# APA106_uno_shield.net
KiCad netlist of a schematic drawn in EAGLE
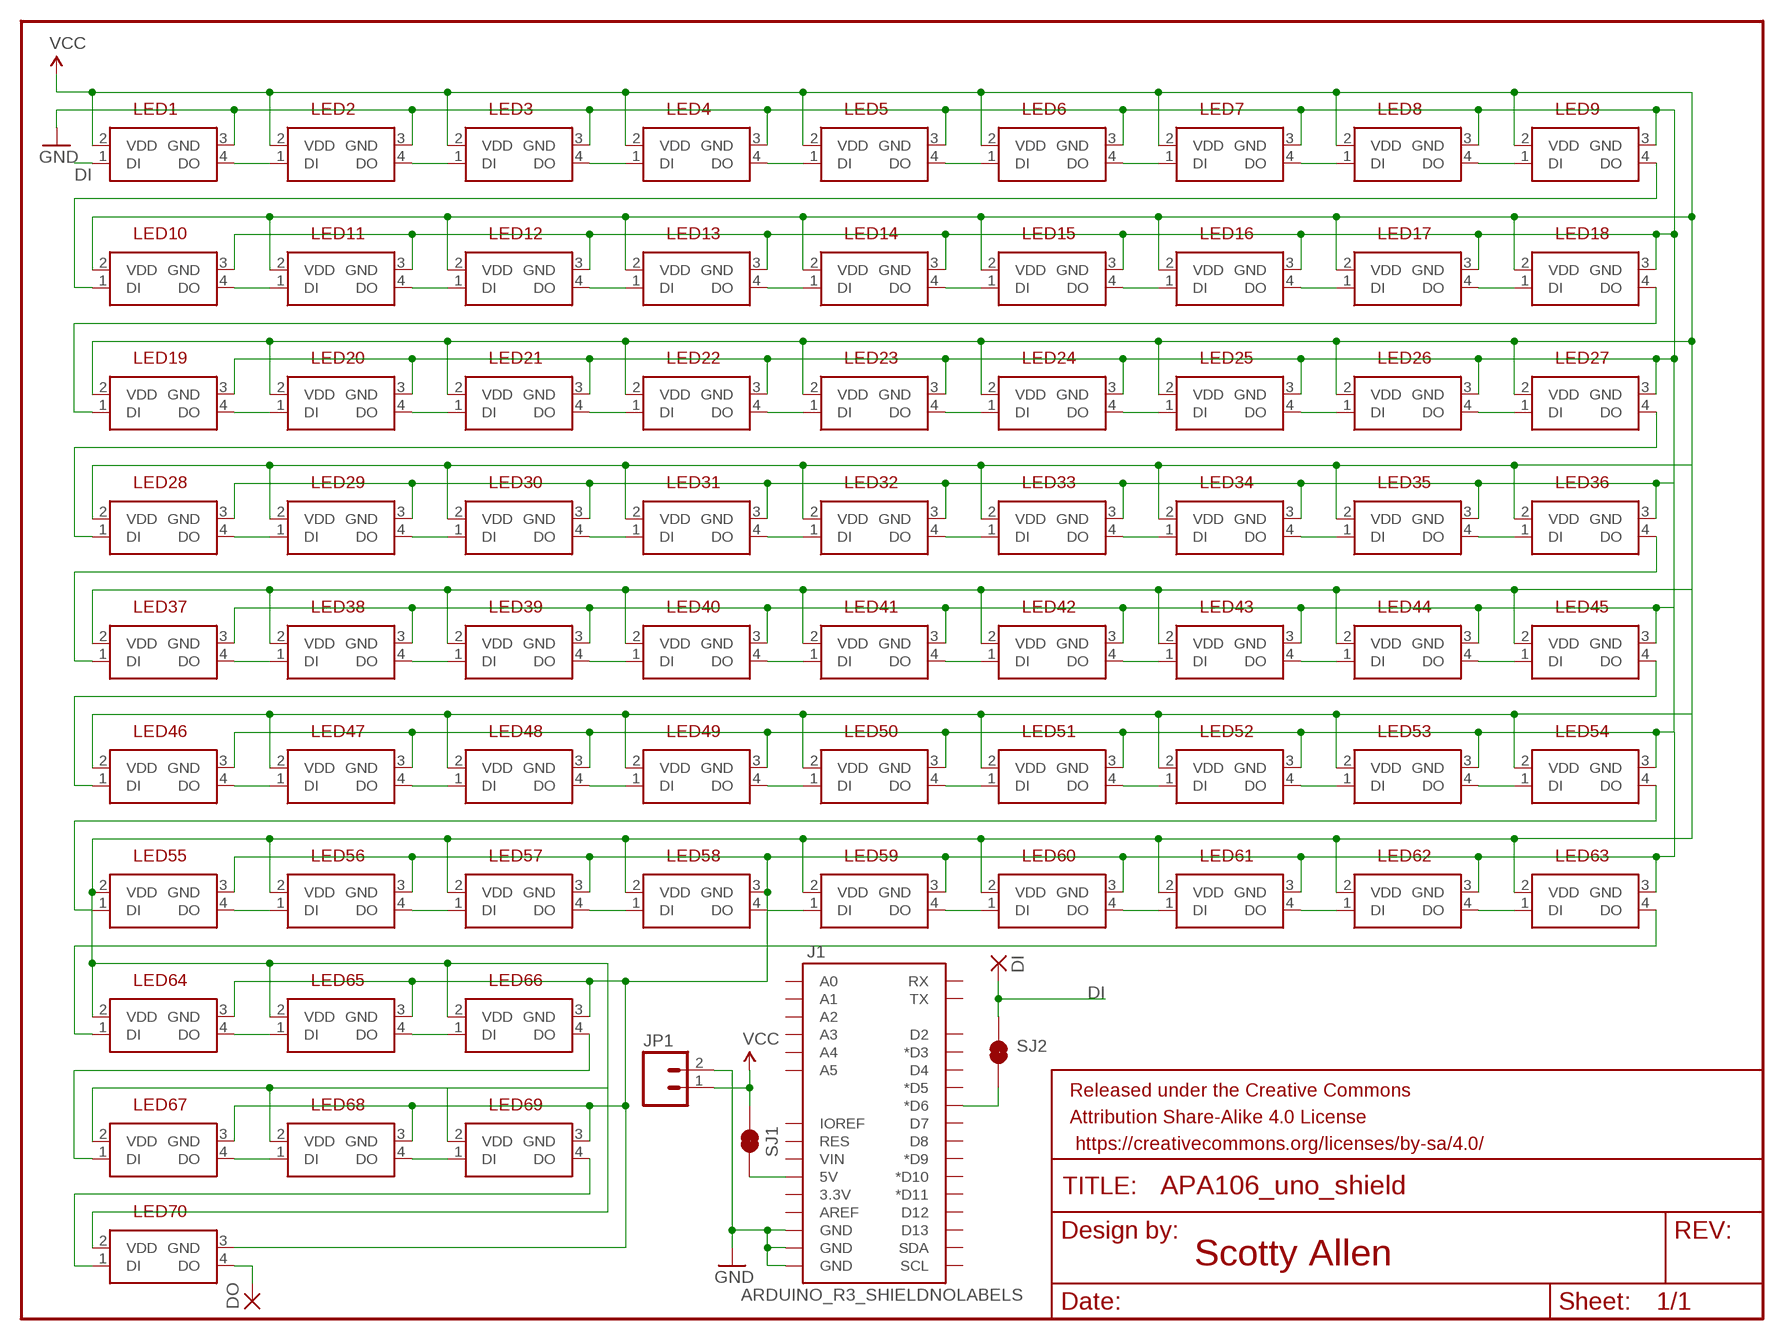
[diagram p0: schematic, sheet 1]

(export (version "E")
  (design (tool "Eeschema 10.0.6"))
  (components
    (comp (ref "DI")
      (value "1,6/0,9")
      (footprint "eagle-import:1,6_0,9")
      (libsource (lib "eagle-import") (part "1,6/0,9"))
    )
    (comp (ref "DO")
      (value "1,6/0,9")
      (footprint "eagle-import:1,6_0,9")
      (libsource (lib "eagle-import") (part "1,6/0,9"))
    )
    (comp (ref "FRAME1")
      (value "FRAME-LETTER")
      (footprint "eagle-import:CREATIVE_COMMONS")
      (libsource (lib "eagle-import") (part "FRAME-LETTER"))
    )
    (comp (ref "J1")
      (value "ARDUINO_R3_SHIELDNOLABELS")
      (footprint "eagle-import:UNO_R3_SHIELD_NOLABELS")
      (libsource (lib "eagle-import") (part "ARDUINO_R3_SHIELDNOLABELS"))
    )
    (comp (ref "JP1")
      (value "M02PTH")
      (footprint "eagle-import:1X02")
      (libsource (lib "eagle-import") (part "M02PTH"))
    )
    (comp (ref "LED1")
      (value "LED-APA106HOLE-OFFSET-SPREAD")
      (footprint "eagle-import:LED-5MM-4PIN-HOLE-OFFSET-SPREAD")
      (libsource (lib "eagle-import") (part "LED-APA106HOLE-OFFSET-SPREAD"))
    )
    (comp (ref "LED2")
      (value "LED-APA106HOLE-OFFSET-SPREAD")
      (footprint "eagle-import:LED-5MM-4PIN-HOLE-OFFSET-SPREAD")
      (libsource (lib "eagle-import") (part "LED-APA106HOLE-OFFSET-SPREAD"))
    )
    (comp (ref "LED3")
      (value "LED-APA106HOLE-OFFSET-SPREAD")
      (footprint "eagle-import:LED-5MM-4PIN-HOLE-OFFSET-SPREAD")
      (libsource (lib "eagle-import") (part "LED-APA106HOLE-OFFSET-SPREAD"))
    )
    (comp (ref "LED4")
      (value "LED-APA106HOLE-OFFSET-SPREAD")
      (footprint "eagle-import:LED-5MM-4PIN-HOLE-OFFSET-SPREAD")
      (libsource (lib "eagle-import") (part "LED-APA106HOLE-OFFSET-SPREAD"))
    )
    (comp (ref "LED5")
      (value "LED-APA106HOLE-OFFSET-SPREAD")
      (footprint "eagle-import:LED-5MM-4PIN-HOLE-OFFSET-SPREAD")
      (libsource (lib "eagle-import") (part "LED-APA106HOLE-OFFSET-SPREAD"))
    )
    (comp (ref "LED6")
      (value "LED-APA106HOLE-OFFSET-SPREAD")
      (footprint "eagle-import:LED-5MM-4PIN-HOLE-OFFSET-SPREAD")
      (libsource (lib "eagle-import") (part "LED-APA106HOLE-OFFSET-SPREAD"))
    )
    (comp (ref "LED7")
      (value "LED-APA106HOLE-OFFSET-SPREAD")
      (footprint "eagle-import:LED-5MM-4PIN-HOLE-OFFSET-SPREAD")
      (libsource (lib "eagle-import") (part "LED-APA106HOLE-OFFSET-SPREAD"))
    )
    (comp (ref "LED8")
      (value "LED-APA106HOLE-OFFSET-SPREAD")
      (footprint "eagle-import:LED-5MM-4PIN-HOLE-OFFSET-SPREAD")
      (libsource (lib "eagle-import") (part "LED-APA106HOLE-OFFSET-SPREAD"))
    )
    (comp (ref "LED9")
      (value "LED-APA106HOLE-OFFSET-SPREAD")
      (footprint "eagle-import:LED-5MM-4PIN-HOLE-OFFSET-SPREAD")
      (libsource (lib "eagle-import") (part "LED-APA106HOLE-OFFSET-SPREAD"))
    )
    (comp (ref "LED10")
      (value "LED-APA106HOLE-OFFSET-SPREAD")
      (footprint "eagle-import:LED-5MM-4PIN-HOLE-OFFSET-SPREAD")
      (libsource (lib "eagle-import") (part "LED-APA106HOLE-OFFSET-SPREAD"))
    )
    (comp (ref "LED11")
      (value "LED-APA106HOLE-OFFSET-SPREAD")
      (footprint "eagle-import:LED-5MM-4PIN-HOLE-OFFSET-SPREAD")
      (libsource (lib "eagle-import") (part "LED-APA106HOLE-OFFSET-SPREAD"))
    )
    (comp (ref "LED12")
      (value "LED-APA106HOLE-OFFSET-SPREAD")
      (footprint "eagle-import:LED-5MM-4PIN-HOLE-OFFSET-SPREAD")
      (libsource (lib "eagle-import") (part "LED-APA106HOLE-OFFSET-SPREAD"))
    )
    (comp (ref "LED13")
      (value "LED-APA106HOLE-OFFSET-SPREAD")
      (footprint "eagle-import:LED-5MM-4PIN-HOLE-OFFSET-SPREAD")
      (libsource (lib "eagle-import") (part "LED-APA106HOLE-OFFSET-SPREAD"))
    )
    (comp (ref "LED14")
      (value "LED-APA106HOLE-OFFSET-SPREAD")
      (footprint "eagle-import:LED-5MM-4PIN-HOLE-OFFSET-SPREAD")
      (libsource (lib "eagle-import") (part "LED-APA106HOLE-OFFSET-SPREAD"))
    )
    (comp (ref "LED15")
      (value "LED-APA106HOLE-OFFSET-SPREAD")
      (footprint "eagle-import:LED-5MM-4PIN-HOLE-OFFSET-SPREAD")
      (libsource (lib "eagle-import") (part "LED-APA106HOLE-OFFSET-SPREAD"))
    )
    (comp (ref "LED16")
      (value "LED-APA106HOLE-OFFSET-SPREAD")
      (footprint "eagle-import:LED-5MM-4PIN-HOLE-OFFSET-SPREAD")
      (libsource (lib "eagle-import") (part "LED-APA106HOLE-OFFSET-SPREAD"))
    )
    (comp (ref "LED17")
      (value "LED-APA106HOLE-OFFSET-SPREAD")
      (footprint "eagle-import:LED-5MM-4PIN-HOLE-OFFSET-SPREAD")
      (libsource (lib "eagle-import") (part "LED-APA106HOLE-OFFSET-SPREAD"))
    )
    (comp (ref "LED18")
      (value "LED-APA106HOLE-OFFSET-SPREAD")
      (footprint "eagle-import:LED-5MM-4PIN-HOLE-OFFSET-SPREAD")
      (libsource (lib "eagle-import") (part "LED-APA106HOLE-OFFSET-SPREAD"))
    )
    (comp (ref "LED19")
      (value "LED-APA106HOLE-OFFSET-SPREAD")
      (footprint "eagle-import:LED-5MM-4PIN-HOLE-OFFSET-SPREAD")
      (libsource (lib "eagle-import") (part "LED-APA106HOLE-OFFSET-SPREAD"))
    )
    (comp (ref "LED20")
      (value "LED-APA106HOLE-OFFSET-SPREAD")
      (footprint "eagle-import:LED-5MM-4PIN-HOLE-OFFSET-SPREAD")
      (libsource (lib "eagle-import") (part "LED-APA106HOLE-OFFSET-SPREAD"))
    )
    (comp (ref "LED21")
      (value "LED-APA106HOLE-OFFSET-SPREAD")
      (footprint "eagle-import:LED-5MM-4PIN-HOLE-OFFSET-SPREAD")
      (libsource (lib "eagle-import") (part "LED-APA106HOLE-OFFSET-SPREAD"))
    )
    (comp (ref "LED22")
      (value "LED-APA106HOLE-OFFSET-SPREAD")
      (footprint "eagle-import:LED-5MM-4PIN-HOLE-OFFSET-SPREAD")
      (libsource (lib "eagle-import") (part "LED-APA106HOLE-OFFSET-SPREAD"))
    )
    (comp (ref "LED23")
      (value "LED-APA106HOLE-OFFSET-SPREAD")
      (footprint "eagle-import:LED-5MM-4PIN-HOLE-OFFSET-SPREAD")
      (libsource (lib "eagle-import") (part "LED-APA106HOLE-OFFSET-SPREAD"))
    )
    (comp (ref "LED24")
      (value "LED-APA106HOLE-OFFSET-SPREAD")
      (footprint "eagle-import:LED-5MM-4PIN-HOLE-OFFSET-SPREAD")
      (libsource (lib "eagle-import") (part "LED-APA106HOLE-OFFSET-SPREAD"))
    )
    (comp (ref "LED25")
      (value "LED-APA106HOLE-OFFSET-SPREAD")
      (footprint "eagle-import:LED-5MM-4PIN-HOLE-OFFSET-SPREAD")
      (libsource (lib "eagle-import") (part "LED-APA106HOLE-OFFSET-SPREAD"))
    )
    (comp (ref "LED26")
      (value "LED-APA106HOLE-OFFSET-SPREAD")
      (footprint "eagle-import:LED-5MM-4PIN-HOLE-OFFSET-SPREAD")
      (libsource (lib "eagle-import") (part "LED-APA106HOLE-OFFSET-SPREAD"))
    )
    (comp (ref "LED27")
      (value "LED-APA106HOLE-OFFSET-SPREAD")
      (footprint "eagle-import:LED-5MM-4PIN-HOLE-OFFSET-SPREAD")
      (libsource (lib "eagle-import") (part "LED-APA106HOLE-OFFSET-SPREAD"))
    )
    (comp (ref "LED28")
      (value "LED-APA106HOLE-OFFSET-SPREAD")
      (footprint "eagle-import:LED-5MM-4PIN-HOLE-OFFSET-SPREAD")
      (libsource (lib "eagle-import") (part "LED-APA106HOLE-OFFSET-SPREAD"))
    )
    (comp (ref "LED29")
      (value "LED-APA106HOLE-OFFSET-SPREAD")
      (footprint "eagle-import:LED-5MM-4PIN-HOLE-OFFSET-SPREAD")
      (libsource (lib "eagle-import") (part "LED-APA106HOLE-OFFSET-SPREAD"))
    )
    (comp (ref "LED30")
      (value "LED-APA106HOLE-OFFSET-SPREAD")
      (footprint "eagle-import:LED-5MM-4PIN-HOLE-OFFSET-SPREAD")
      (libsource (lib "eagle-import") (part "LED-APA106HOLE-OFFSET-SPREAD"))
    )
    (comp (ref "LED31")
      (value "LED-APA106HOLE-OFFSET-SPREAD")
      (footprint "eagle-import:LED-5MM-4PIN-HOLE-OFFSET-SPREAD")
      (libsource (lib "eagle-import") (part "LED-APA106HOLE-OFFSET-SPREAD"))
    )
    (comp (ref "LED32")
      (value "LED-APA106HOLE-OFFSET-SPREAD")
      (footprint "eagle-import:LED-5MM-4PIN-HOLE-OFFSET-SPREAD")
      (libsource (lib "eagle-import") (part "LED-APA106HOLE-OFFSET-SPREAD"))
    )
    (comp (ref "LED33")
      (value "LED-APA106HOLE-OFFSET-SPREAD")
      (footprint "eagle-import:LED-5MM-4PIN-HOLE-OFFSET-SPREAD")
      (libsource (lib "eagle-import") (part "LED-APA106HOLE-OFFSET-SPREAD"))
    )
    (comp (ref "LED34")
      (value "LED-APA106HOLE-OFFSET-SPREAD")
      (footprint "eagle-import:LED-5MM-4PIN-HOLE-OFFSET-SPREAD")
      (libsource (lib "eagle-import") (part "LED-APA106HOLE-OFFSET-SPREAD"))
    )
    (comp (ref "LED35")
      (value "LED-APA106HOLE-OFFSET-SPREAD")
      (footprint "eagle-import:LED-5MM-4PIN-HOLE-OFFSET-SPREAD")
      (libsource (lib "eagle-import") (part "LED-APA106HOLE-OFFSET-SPREAD"))
    )
    (comp (ref "LED36")
      (value "LED-APA106HOLE-OFFSET-SPREAD")
      (footprint "eagle-import:LED-5MM-4PIN-HOLE-OFFSET-SPREAD")
      (libsource (lib "eagle-import") (part "LED-APA106HOLE-OFFSET-SPREAD"))
    )
    (comp (ref "LED37")
      (value "LED-APA106HOLE-OFFSET-SPREAD")
      (footprint "eagle-import:LED-5MM-4PIN-HOLE-OFFSET-SPREAD")
      (libsource (lib "eagle-import") (part "LED-APA106HOLE-OFFSET-SPREAD"))
    )
    (comp (ref "LED38")
      (value "LED-APA106HOLE-OFFSET-SPREAD")
      (footprint "eagle-import:LED-5MM-4PIN-HOLE-OFFSET-SPREAD")
      (libsource (lib "eagle-import") (part "LED-APA106HOLE-OFFSET-SPREAD"))
    )
    (comp (ref "LED39")
      (value "LED-APA106HOLE-OFFSET-SPREAD")
      (footprint "eagle-import:LED-5MM-4PIN-HOLE-OFFSET-SPREAD")
      (libsource (lib "eagle-import") (part "LED-APA106HOLE-OFFSET-SPREAD"))
    )
    (comp (ref "LED40")
      (value "LED-APA106HOLE-OFFSET-SPREAD")
      (footprint "eagle-import:LED-5MM-4PIN-HOLE-OFFSET-SPREAD")
      (libsource (lib "eagle-import") (part "LED-APA106HOLE-OFFSET-SPREAD"))
    )
    (comp (ref "LED41")
      (value "LED-APA106HOLE-OFFSET-SPREAD")
      (footprint "eagle-import:LED-5MM-4PIN-HOLE-OFFSET-SPREAD")
      (libsource (lib "eagle-import") (part "LED-APA106HOLE-OFFSET-SPREAD"))
    )
    (comp (ref "LED42")
      (value "LED-APA106HOLE-OFFSET-SPREAD")
      (footprint "eagle-import:LED-5MM-4PIN-HOLE-OFFSET-SPREAD")
      (libsource (lib "eagle-import") (part "LED-APA106HOLE-OFFSET-SPREAD"))
    )
    (comp (ref "LED43")
      (value "LED-APA106HOLE-OFFSET-SPREAD")
      (footprint "eagle-import:LED-5MM-4PIN-HOLE-OFFSET-SPREAD")
      (libsource (lib "eagle-import") (part "LED-APA106HOLE-OFFSET-SPREAD"))
    )
    (comp (ref "LED44")
      (value "LED-APA106HOLE-OFFSET-SPREAD")
      (footprint "eagle-import:LED-5MM-4PIN-HOLE-OFFSET-SPREAD")
      (libsource (lib "eagle-import") (part "LED-APA106HOLE-OFFSET-SPREAD"))
    )
    (comp (ref "LED45")
      (value "LED-APA106HOLE-OFFSET-SPREAD")
      (footprint "eagle-import:LED-5MM-4PIN-HOLE-OFFSET-SPREAD")
      (libsource (lib "eagle-import") (part "LED-APA106HOLE-OFFSET-SPREAD"))
    )
    (comp (ref "LED46")
      (value "LED-APA106HOLE-OFFSET-SPREAD")
      (footprint "eagle-import:LED-5MM-4PIN-HOLE-OFFSET-SPREAD")
      (libsource (lib "eagle-import") (part "LED-APA106HOLE-OFFSET-SPREAD"))
    )
    (comp (ref "LED47")
      (value "LED-APA106HOLE-OFFSET-SPREAD")
      (footprint "eagle-import:LED-5MM-4PIN-HOLE-OFFSET-SPREAD")
      (libsource (lib "eagle-import") (part "LED-APA106HOLE-OFFSET-SPREAD"))
    )
    (comp (ref "LED48")
      (value "LED-APA106HOLE-OFFSET-SPREAD")
      (footprint "eagle-import:LED-5MM-4PIN-HOLE-OFFSET-SPREAD")
      (libsource (lib "eagle-import") (part "LED-APA106HOLE-OFFSET-SPREAD"))
    )
    (comp (ref "LED49")
      (value "LED-APA106HOLE-OFFSET-SPREAD")
      (footprint "eagle-import:LED-5MM-4PIN-HOLE-OFFSET-SPREAD")
      (libsource (lib "eagle-import") (part "LED-APA106HOLE-OFFSET-SPREAD"))
    )
    (comp (ref "LED50")
      (value "LED-APA106HOLE-OFFSET-SPREAD")
      (footprint "eagle-import:LED-5MM-4PIN-HOLE-OFFSET-SPREAD")
      (libsource (lib "eagle-import") (part "LED-APA106HOLE-OFFSET-SPREAD"))
    )
    (comp (ref "LED51")
      (value "LED-APA106HOLE-OFFSET-SPREAD")
      (footprint "eagle-import:LED-5MM-4PIN-HOLE-OFFSET-SPREAD")
      (libsource (lib "eagle-import") (part "LED-APA106HOLE-OFFSET-SPREAD"))
    )
    (comp (ref "LED52")
      (value "LED-APA106HOLE-OFFSET-SPREAD")
      (footprint "eagle-import:LED-5MM-4PIN-HOLE-OFFSET-SPREAD")
      (libsource (lib "eagle-import") (part "LED-APA106HOLE-OFFSET-SPREAD"))
    )
    (comp (ref "LED53")
      (value "LED-APA106HOLE-OFFSET-SPREAD")
      (footprint "eagle-import:LED-5MM-4PIN-HOLE-OFFSET-SPREAD")
      (libsource (lib "eagle-import") (part "LED-APA106HOLE-OFFSET-SPREAD"))
    )
    (comp (ref "LED54")
      (value "LED-APA106HOLE-OFFSET-SPREAD")
      (footprint "eagle-import:LED-5MM-4PIN-HOLE-OFFSET-SPREAD")
      (libsource (lib "eagle-import") (part "LED-APA106HOLE-OFFSET-SPREAD"))
    )
    (comp (ref "LED55")
      (value "LED-APA106HOLE-OFFSET-SPREAD")
      (footprint "eagle-import:LED-5MM-4PIN-HOLE-OFFSET-SPREAD")
      (libsource (lib "eagle-import") (part "LED-APA106HOLE-OFFSET-SPREAD"))
    )
    (comp (ref "LED56")
      (value "LED-APA106HOLE-OFFSET-SPREAD")
      (footprint "eagle-import:LED-5MM-4PIN-HOLE-OFFSET-SPREAD")
      (libsource (lib "eagle-import") (part "LED-APA106HOLE-OFFSET-SPREAD"))
    )
    (comp (ref "LED57")
      (value "LED-APA106HOLE-OFFSET-SPREAD")
      (footprint "eagle-import:LED-5MM-4PIN-HOLE-OFFSET-SPREAD")
      (libsource (lib "eagle-import") (part "LED-APA106HOLE-OFFSET-SPREAD"))
    )
    (comp (ref "LED58")
      (value "LED-APA106HOLE-OFFSET-SPREAD")
      (footprint "eagle-import:LED-5MM-4PIN-HOLE-OFFSET-SPREAD")
      (libsource (lib "eagle-import") (part "LED-APA106HOLE-OFFSET-SPREAD"))
    )
    (comp (ref "LED59")
      (value "LED-APA106HOLE-OFFSET-SPREAD")
      (footprint "eagle-import:LED-5MM-4PIN-HOLE-OFFSET-SPREAD")
      (libsource (lib "eagle-import") (part "LED-APA106HOLE-OFFSET-SPREAD"))
    )
    (comp (ref "LED60")
      (value "LED-APA106HOLE-OFFSET-SPREAD")
      (footprint "eagle-import:LED-5MM-4PIN-HOLE-OFFSET-SPREAD")
      (libsource (lib "eagle-import") (part "LED-APA106HOLE-OFFSET-SPREAD"))
    )
    (comp (ref "LED61")
      (value "LED-APA106HOLE-OFFSET-SPREAD")
      (footprint "eagle-import:LED-5MM-4PIN-HOLE-OFFSET-SPREAD")
      (libsource (lib "eagle-import") (part "LED-APA106HOLE-OFFSET-SPREAD"))
    )
    (comp (ref "LED62")
      (value "LED-APA106HOLE-OFFSET-SPREAD")
      (footprint "eagle-import:LED-5MM-4PIN-HOLE-OFFSET-SPREAD")
      (libsource (lib "eagle-import") (part "LED-APA106HOLE-OFFSET-SPREAD"))
    )
    (comp (ref "LED63")
      (value "LED-APA106HOLE-OFFSET-SPREAD")
      (footprint "eagle-import:LED-5MM-4PIN-HOLE-OFFSET-SPREAD")
      (libsource (lib "eagle-import") (part "LED-APA106HOLE-OFFSET-SPREAD"))
    )
    (comp (ref "LED64")
      (value "LED-APA106HOLE-OFFSET-SPREAD")
      (footprint "eagle-import:LED-5MM-4PIN-HOLE-OFFSET-SPREAD")
      (libsource (lib "eagle-import") (part "LED-APA106HOLE-OFFSET-SPREAD"))
    )
    (comp (ref "LED65")
      (value "LED-APA106HOLE-OFFSET-SPREAD")
      (footprint "eagle-import:LED-5MM-4PIN-HOLE-OFFSET-SPREAD")
      (libsource (lib "eagle-import") (part "LED-APA106HOLE-OFFSET-SPREAD"))
    )
    (comp (ref "LED66")
      (value "LED-APA106HOLE-OFFSET-SPREAD")
      (footprint "eagle-import:LED-5MM-4PIN-HOLE-OFFSET-SPREAD")
      (libsource (lib "eagle-import") (part "LED-APA106HOLE-OFFSET-SPREAD"))
    )
    (comp (ref "LED67")
      (value "LED-APA106HOLE-OFFSET-SPREAD")
      (footprint "eagle-import:LED-5MM-4PIN-HOLE-OFFSET-SPREAD")
      (libsource (lib "eagle-import") (part "LED-APA106HOLE-OFFSET-SPREAD"))
    )
    (comp (ref "LED68")
      (value "LED-APA106HOLE-OFFSET-SPREAD")
      (footprint "eagle-import:LED-5MM-4PIN-HOLE-OFFSET-SPREAD")
      (libsource (lib "eagle-import") (part "LED-APA106HOLE-OFFSET-SPREAD"))
    )
    (comp (ref "LED69")
      (value "LED-APA106HOLE-OFFSET-SPREAD")
      (footprint "eagle-import:LED-5MM-4PIN-HOLE-OFFSET-SPREAD")
      (libsource (lib "eagle-import") (part "LED-APA106HOLE-OFFSET-SPREAD"))
    )
    (comp (ref "LED70")
      (value "LED-APA106HOLE-OFFSET-SPREAD")
      (footprint "eagle-import:LED-5MM-4PIN-HOLE-OFFSET-SPREAD")
      (libsource (lib "eagle-import") (part "LED-APA106HOLE-OFFSET-SPREAD"))
    )
    (comp (ref "SJ1")
      (value "JUMPER-PAD-2-NC_BY_TRACENO_SILK")
      (footprint "eagle-import:PAD-JUMPER-2-NC_BY_TRACE_NO_SILK")
      (libsource (lib "eagle-import") (part "JUMPER-PAD-2-NC_BY_TRACENO_SILK"))
    )
    (comp (ref "SJ2")
      (value "JUMPER-PAD-2-NC_BY_TRACENO_SILK")
      (footprint "eagle-import:PAD-JUMPER-2-NC_BY_TRACE_NO_SILK")
      (libsource (lib "eagle-import") (part "JUMPER-PAD-2-NC_BY_TRACENO_SILK"))
    )
  )
  (nets
    (net (code "1") (name "/DI") (class "Default")
      (node (ref "DI") (pin "1") (pinfunction "P_1") (pintype "passive"))
      (node (ref "LED1") (pin "1") (pinfunction "DI_1") (pintype "input"))
      (node (ref "SJ2") (pin "2") (pinfunction "2_2") (pintype "passive"))
    )
    (net (code "2") (name "GND") (class "Default")
      (node (ref "J1") (pin "GND@0") (pinfunction "GND_GND@0") (pintype "bidirectional"))
      (node (ref "J1") (pin "GND@1") (pinfunction "GND_GND@1") (pintype "bidirectional"))
      (node (ref "J1") (pin "GND@2") (pinfunction "GND_GND@2") (pintype "bidirectional"))
      (node (ref "JP1") (pin "2") (pinfunction "2_2") (pintype "passive"))
      (node (ref "LED1") (pin "3") (pinfunction "GND_3") (pintype "power_in"))
      (node (ref "LED10") (pin "3") (pinfunction "GND_3") (pintype "power_in"))
      (node (ref "LED11") (pin "3") (pinfunction "GND_3") (pintype "power_in"))
      (node (ref "LED12") (pin "3") (pinfunction "GND_3") (pintype "power_in"))
      (node (ref "LED13") (pin "3") (pinfunction "GND_3") (pintype "power_in"))
      (node (ref "LED14") (pin "3") (pinfunction "GND_3") (pintype "power_in"))
      (node (ref "LED15") (pin "3") (pinfunction "GND_3") (pintype "power_in"))
      (node (ref "LED16") (pin "3") (pinfunction "GND_3") (pintype "power_in"))
      (node (ref "LED17") (pin "3") (pinfunction "GND_3") (pintype "power_in"))
      (node (ref "LED18") (pin "3") (pinfunction "GND_3") (pintype "power_in"))
      (node (ref "LED19") (pin "3") (pinfunction "GND_3") (pintype "power_in"))
      (node (ref "LED2") (pin "3") (pinfunction "GND_3") (pintype "power_in"))
      (node (ref "LED20") (pin "3") (pinfunction "GND_3") (pintype "power_in"))
      (node (ref "LED21") (pin "3") (pinfunction "GND_3") (pintype "power_in"))
      (node (ref "LED22") (pin "3") (pinfunction "GND_3") (pintype "power_in"))
      (node (ref "LED23") (pin "3") (pinfunction "GND_3") (pintype "power_in"))
      (node (ref "LED24") (pin "3") (pinfunction "GND_3") (pintype "power_in"))
      (node (ref "LED25") (pin "3") (pinfunction "GND_3") (pintype "power_in"))
      (node (ref "LED26") (pin "3") (pinfunction "GND_3") (pintype "power_in"))
      (node (ref "LED27") (pin "3") (pinfunction "GND_3") (pintype "power_in"))
      (node (ref "LED28") (pin "3") (pinfunction "GND_3") (pintype "power_in"))
      (node (ref "LED29") (pin "3") (pinfunction "GND_3") (pintype "power_in"))
      (node (ref "LED3") (pin "3") (pinfunction "GND_3") (pintype "power_in"))
      (node (ref "LED30") (pin "3") (pinfunction "GND_3") (pintype "power_in"))
      (node (ref "LED31") (pin "3") (pinfunction "GND_3") (pintype "power_in"))
      (node (ref "LED32") (pin "3") (pinfunction "GND_3") (pintype "power_in"))
      (node (ref "LED33") (pin "3") (pinfunction "GND_3") (pintype "power_in"))
      (node (ref "LED34") (pin "3") (pinfunction "GND_3") (pintype "power_in"))
      (node (ref "LED35") (pin "3") (pinfunction "GND_3") (pintype "power_in"))
      (node (ref "LED36") (pin "3") (pinfunction "GND_3") (pintype "power_in"))
      (node (ref "LED37") (pin "3") (pinfunction "GND_3") (pintype "power_in"))
      (node (ref "LED38") (pin "3") (pinfunction "GND_3") (pintype "power_in"))
      (node (ref "LED39") (pin "3") (pinfunction "GND_3") (pintype "power_in"))
      (node (ref "LED4") (pin "3") (pinfunction "GND_3") (pintype "power_in"))
      (node (ref "LED40") (pin "3") (pinfunction "GND_3") (pintype "power_in"))
      (node (ref "LED41") (pin "3") (pinfunction "GND_3") (pintype "power_in"))
      (node (ref "LED42") (pin "3") (pinfunction "GND_3") (pintype "power_in"))
      (node (ref "LED43") (pin "3") (pinfunction "GND_3") (pintype "power_in"))
      (node (ref "LED44") (pin "3") (pinfunction "GND_3") (pintype "power_in"))
      (node (ref "LED45") (pin "3") (pinfunction "GND_3") (pintype "power_in"))
      (node (ref "LED46") (pin "3") (pinfunction "GND_3") (pintype "power_in"))
      (node (ref "LED47") (pin "3") (pinfunction "GND_3") (pintype "power_in"))
      (node (ref "LED48") (pin "3") (pinfunction "GND_3") (pintype "power_in"))
      (node (ref "LED49") (pin "3") (pinfunction "GND_3") (pintype "power_in"))
      (node (ref "LED5") (pin "3") (pinfunction "GND_3") (pintype "power_in"))
      (node (ref "LED50") (pin "3") (pinfunction "GND_3") (pintype "power_in"))
      (node (ref "LED51") (pin "3") (pinfunction "GND_3") (pintype "power_in"))
      (node (ref "LED52") (pin "3") (pinfunction "GND_3") (pintype "power_in"))
      (node (ref "LED53") (pin "3") (pinfunction "GND_3") (pintype "power_in"))
      (node (ref "LED54") (pin "3") (pinfunction "GND_3") (pintype "power_in"))
      (node (ref "LED55") (pin "3") (pinfunction "GND_3") (pintype "power_in"))
      (node (ref "LED56") (pin "3") (pinfunction "GND_3") (pintype "power_in"))
      (node (ref "LED57") (pin "3") (pinfunction "GND_3") (pintype "power_in"))
      (node (ref "LED58") (pin "3") (pinfunction "GND_3") (pintype "power_in"))
      (node (ref "LED59") (pin "3") (pinfunction "GND_3") (pintype "power_in"))
      (node (ref "LED6") (pin "3") (pinfunction "GND_3") (pintype "power_in"))
      (node (ref "LED60") (pin "3") (pinfunction "GND_3") (pintype "power_in"))
      (node (ref "LED61") (pin "3") (pinfunction "GND_3") (pintype "power_in"))
      (node (ref "LED62") (pin "3") (pinfunction "GND_3") (pintype "power_in"))
      (node (ref "LED63") (pin "3") (pinfunction "GND_3") (pintype "power_in"))
      (node (ref "LED64") (pin "3") (pinfunction "GND_3") (pintype "power_in"))
      (node (ref "LED65") (pin "3") (pinfunction "GND_3") (pintype "power_in"))
      (node (ref "LED66") (pin "3") (pinfunction "GND_3") (pintype "power_in"))
      (node (ref "LED67") (pin "3") (pinfunction "GND_3") (pintype "power_in"))
      (node (ref "LED68") (pin "3") (pinfunction "GND_3") (pintype "power_in"))
      (node (ref "LED69") (pin "3") (pinfunction "GND_3") (pintype "power_in"))
      (node (ref "LED7") (pin "3") (pinfunction "GND_3") (pintype "power_in"))
      (node (ref "LED70") (pin "3") (pinfunction "GND_3") (pintype "power_in"))
      (node (ref "LED8") (pin "3") (pinfunction "GND_3") (pintype "power_in"))
      (node (ref "LED9") (pin "3") (pinfunction "GND_3") (pintype "power_in"))
    )
    (net (code "3") (name "Net-(DO-P)") (class "Default")
      (node (ref "DO") (pin "1") (pinfunction "P_1") (pintype "passive"))
      (node (ref "LED70") (pin "4") (pinfunction "DO_4") (pintype "output"))
    )
    (net (code "4") (name "Net-(J1-*D6)") (class "Default")
      (node (ref "J1") (pin "D6") (pinfunction "*D6_D6") (pintype "bidirectional"))
      (node (ref "SJ2") (pin "1") (pinfunction "1_1") (pintype "passive"))
    )
    (net (code "5") (name "Net-(J1-Pad5V)") (class "Default")
      (node (ref "J1") (pin "5V") (pinfunction "5V_5V") (pintype "bidirectional"))
      (node (ref "SJ1") (pin "1") (pinfunction "1_1") (pintype "passive"))
    )
    (net (code "6") (name "Net-(LED1-DO)") (class "Default")
      (node (ref "LED1") (pin "4") (pinfunction "DO_4") (pintype "output"))
      (node (ref "LED2") (pin "1") (pinfunction "DI_1") (pintype "input"))
    )
    (net (code "7") (name "Net-(LED2-DO)") (class "Default")
      (node (ref "LED2") (pin "4") (pinfunction "DO_4") (pintype "output"))
      (node (ref "LED3") (pin "1") (pinfunction "DI_1") (pintype "input"))
    )
    (net (code "8") (name "Net-(LED3-DO)") (class "Default")
      (node (ref "LED3") (pin "4") (pinfunction "DO_4") (pintype "output"))
      (node (ref "LED4") (pin "1") (pinfunction "DI_1") (pintype "input"))
    )
    (net (code "9") (name "Net-(LED4-DO)") (class "Default")
      (node (ref "LED4") (pin "4") (pinfunction "DO_4") (pintype "output"))
      (node (ref "LED5") (pin "1") (pinfunction "DI_1") (pintype "input"))
    )
    (net (code "10") (name "Net-(LED5-DO)") (class "Default")
      (node (ref "LED5") (pin "4") (pinfunction "DO_4") (pintype "output"))
      (node (ref "LED6") (pin "1") (pinfunction "DI_1") (pintype "input"))
    )
    (net (code "11") (name "Net-(LED6-DO)") (class "Default")
      (node (ref "LED6") (pin "4") (pinfunction "DO_4") (pintype "output"))
      (node (ref "LED7") (pin "1") (pinfunction "DI_1") (pintype "input"))
    )
    (net (code "12") (name "Net-(LED7-DO)") (class "Default")
      (node (ref "LED7") (pin "4") (pinfunction "DO_4") (pintype "output"))
      (node (ref "LED8") (pin "1") (pinfunction "DI_1") (pintype "input"))
    )
    (net (code "13") (name "Net-(LED8-DO)") (class "Default")
      (node (ref "LED8") (pin "4") (pinfunction "DO_4") (pintype "output"))
      (node (ref "LED9") (pin "1") (pinfunction "DI_1") (pintype "input"))
    )
    (net (code "14") (name "Net-(LED10-DI)") (class "Default")
      (node (ref "LED10") (pin "1") (pinfunction "DI_1") (pintype "input"))
      (node (ref "LED9") (pin "4") (pinfunction "DO_4") (pintype "output"))
    )
    (net (code "15") (name "Net-(LED10-DO)") (class "Default")
      (node (ref "LED10") (pin "4") (pinfunction "DO_4") (pintype "output"))
      (node (ref "LED11") (pin "1") (pinfunction "DI_1") (pintype "input"))
    )
    (net (code "16") (name "Net-(LED11-DO)") (class "Default")
      (node (ref "LED11") (pin "4") (pinfunction "DO_4") (pintype "output"))
      (node (ref "LED12") (pin "1") (pinfunction "DI_1") (pintype "input"))
    )
    (net (code "17") (name "Net-(LED12-DO)") (class "Default")
      (node (ref "LED12") (pin "4") (pinfunction "DO_4") (pintype "output"))
      (node (ref "LED13") (pin "1") (pinfunction "DI_1") (pintype "input"))
    )
    (net (code "18") (name "Net-(LED13-DO)") (class "Default")
      (node (ref "LED13") (pin "4") (pinfunction "DO_4") (pintype "output"))
      (node (ref "LED14") (pin "1") (pinfunction "DI_1") (pintype "input"))
    )
    (net (code "19") (name "Net-(LED14-DO)") (class "Default")
      (node (ref "LED14") (pin "4") (pinfunction "DO_4") (pintype "output"))
      (node (ref "LED15") (pin "1") (pinfunction "DI_1") (pintype "input"))
    )
    (net (code "20") (name "Net-(LED15-DO)") (class "Default")
      (node (ref "LED15") (pin "4") (pinfunction "DO_4") (pintype "output"))
      (node (ref "LED16") (pin "1") (pinfunction "DI_1") (pintype "input"))
    )
    (net (code "21") (name "Net-(LED16-DO)") (class "Default")
      (node (ref "LED16") (pin "4") (pinfunction "DO_4") (pintype "output"))
      (node (ref "LED17") (pin "1") (pinfunction "DI_1") (pintype "input"))
    )
    (net (code "22") (name "Net-(LED17-DO)") (class "Default")
      (node (ref "LED17") (pin "4") (pinfunction "DO_4") (pintype "output"))
      (node (ref "LED18") (pin "1") (pinfunction "DI_1") (pintype "input"))
    )
    (net (code "23") (name "Net-(LED18-DO)") (class "Default")
      (node (ref "LED18") (pin "4") (pinfunction "DO_4") (pintype "output"))
      (node (ref "LED19") (pin "1") (pinfunction "DI_1") (pintype "input"))
    )
    (net (code "24") (name "Net-(LED19-DO)") (class "Default")
      (node (ref "LED19") (pin "4") (pinfunction "DO_4") (pintype "output"))
      (node (ref "LED20") (pin "1") (pinfunction "DI_1") (pintype "input"))
    )
    (net (code "25") (name "Net-(LED20-DO)") (class "Default")
      (node (ref "LED20") (pin "4") (pinfunction "DO_4") (pintype "output"))
      (node (ref "LED21") (pin "1") (pinfunction "DI_1") (pintype "input"))
    )
    (net (code "26") (name "Net-(LED21-DO)") (class "Default")
      (node (ref "LED21") (pin "4") (pinfunction "DO_4") (pintype "output"))
      (node (ref "LED22") (pin "1") (pinfunction "DI_1") (pintype "input"))
    )
    (net (code "27") (name "Net-(LED22-DO)") (class "Default")
      (node (ref "LED22") (pin "4") (pinfunction "DO_4") (pintype "output"))
      (node (ref "LED23") (pin "1") (pinfunction "DI_1") (pintype "input"))
    )
    (net (code "28") (name "Net-(LED23-DO)") (class "Default")
      (node (ref "LED23") (pin "4") (pinfunction "DO_4") (pintype "output"))
      (node (ref "LED24") (pin "1") (pinfunction "DI_1") (pintype "input"))
    )
    (net (code "29") (name "Net-(LED24-DO)") (class "Default")
      (node (ref "LED24") (pin "4") (pinfunction "DO_4") (pintype "output"))
      (node (ref "LED25") (pin "1") (pinfunction "DI_1") (pintype "input"))
    )
    (net (code "30") (name "Net-(LED25-DO)") (class "Default")
      (node (ref "LED25") (pin "4") (pinfunction "DO_4") (pintype "output"))
      (node (ref "LED26") (pin "1") (pinfunction "DI_1") (pintype "input"))
    )
    (net (code "31") (name "Net-(LED26-DO)") (class "Default")
      (node (ref "LED26") (pin "4") (pinfunction "DO_4") (pintype "output"))
      (node (ref "LED27") (pin "1") (pinfunction "DI_1") (pintype "input"))
    )
    (net (code "32") (name "Net-(LED27-DO)") (class "Default")
      (node (ref "LED27") (pin "4") (pinfunction "DO_4") (pintype "output"))
      (node (ref "LED28") (pin "1") (pinfunction "DI_1") (pintype "input"))
    )
    (net (code "33") (name "Net-(LED28-DO)") (class "Default")
      (node (ref "LED28") (pin "4") (pinfunction "DO_4") (pintype "output"))
      (node (ref "LED29") (pin "1") (pinfunction "DI_1") (pintype "input"))
    )
    (net (code "34") (name "Net-(LED29-DO)") (class "Default")
      (node (ref "LED29") (pin "4") (pinfunction "DO_4") (pintype "output"))
      (node (ref "LED30") (pin "1") (pinfunction "DI_1") (pintype "input"))
    )
    (net (code "35") (name "Net-(LED30-DO)") (class "Default")
      (node (ref "LED30") (pin "4") (pinfunction "DO_4") (pintype "output"))
      (node (ref "LED31") (pin "1") (pinfunction "DI_1") (pintype "input"))
    )
    (net (code "36") (name "Net-(LED31-DO)") (class "Default")
      (node (ref "LED31") (pin "4") (pinfunction "DO_4") (pintype "output"))
      (node (ref "LED32") (pin "1") (pinfunction "DI_1") (pintype "input"))
    )
    (net (code "37") (name "Net-(LED32-DO)") (class "Default")
      (node (ref "LED32") (pin "4") (pinfunction "DO_4") (pintype "output"))
      (node (ref "LED33") (pin "1") (pinfunction "DI_1") (pintype "input"))
    )
    (net (code "38") (name "Net-(LED33-DO)") (class "Default")
      (node (ref "LED33") (pin "4") (pinfunction "DO_4") (pintype "output"))
      (node (ref "LED34") (pin "1") (pinfunction "DI_1") (pintype "input"))
    )
    (net (code "39") (name "Net-(LED34-DO)") (class "Default")
      (node (ref "LED34") (pin "4") (pinfunction "DO_4") (pintype "output"))
      (node (ref "LED35") (pin "1") (pinfunction "DI_1") (pintype "input"))
    )
    (net (code "40") (name "Net-(LED35-DO)") (class "Default")
      (node (ref "LED35") (pin "4") (pinfunction "DO_4") (pintype "output"))
      (node (ref "LED36") (pin "1") (pinfunction "DI_1") (pintype "input"))
    )
    (net (code "41") (name "Net-(LED36-DO)") (class "Default")
      (node (ref "LED36") (pin "4") (pinfunction "DO_4") (pintype "output"))
      (node (ref "LED37") (pin "1") (pinfunction "DI_1") (pintype "input"))
    )
    (net (code "42") (name "Net-(LED37-DO)") (class "Default")
      (node (ref "LED37") (pin "4") (pinfunction "DO_4") (pintype "output"))
      (node (ref "LED38") (pin "1") (pinfunction "DI_1") (pintype "input"))
    )
    (net (code "43") (name "Net-(LED38-DO)") (class "Default")
      (node (ref "LED38") (pin "4") (pinfunction "DO_4") (pintype "output"))
      (node (ref "LED39") (pin "1") (pinfunction "DI_1") (pintype "input"))
    )
    (net (code "44") (name "Net-(LED39-DO)") (class "Default")
      (node (ref "LED39") (pin "4") (pinfunction "DO_4") (pintype "output"))
      (node (ref "LED40") (pin "1") (pinfunction "DI_1") (pintype "input"))
    )
    (net (code "45") (name "Net-(LED40-DO)") (class "Default")
      (node (ref "LED40") (pin "4") (pinfunction "DO_4") (pintype "output"))
      (node (ref "LED41") (pin "1") (pinfunction "DI_1") (pintype "input"))
    )
    (net (code "46") (name "Net-(LED41-DO)") (class "Default")
      (node (ref "LED41") (pin "4") (pinfunction "DO_4") (pintype "output"))
      (node (ref "LED42") (pin "1") (pinfunction "DI_1") (pintype "input"))
    )
    (net (code "47") (name "Net-(LED42-DO)") (class "Default")
      (node (ref "LED42") (pin "4") (pinfunction "DO_4") (pintype "output"))
      (node (ref "LED43") (pin "1") (pinfunction "DI_1") (pintype "input"))
    )
    (net (code "48") (name "Net-(LED43-DO)") (class "Default")
      (node (ref "LED43") (pin "4") (pinfunction "DO_4") (pintype "output"))
      (node (ref "LED44") (pin "1") (pinfunction "DI_1") (pintype "input"))
    )
    (net (code "49") (name "Net-(LED44-DO)") (class "Default")
      (node (ref "LED44") (pin "4") (pinfunction "DO_4") (pintype "output"))
      (node (ref "LED45") (pin "1") (pinfunction "DI_1") (pintype "input"))
    )
    (net (code "50") (name "Net-(LED45-DO)") (class "Default")
      (node (ref "LED45") (pin "4") (pinfunction "DO_4") (pintype "output"))
      (node (ref "LED46") (pin "1") (pinfunction "DI_1") (pintype "input"))
    )
    (net (code "51") (name "Net-(LED46-DO)") (class "Default")
      (node (ref "LED46") (pin "4") (pinfunction "DO_4") (pintype "output"))
      (node (ref "LED47") (pin "1") (pinfunction "DI_1") (pintype "input"))
    )
    (net (code "52") (name "Net-(LED47-DO)") (class "Default")
      (node (ref "LED47") (pin "4") (pinfunction "DO_4") (pintype "output"))
      (node (ref "LED48") (pin "1") (pinfunction "DI_1") (pintype "input"))
    )
    (net (code "53") (name "Net-(LED48-DO)") (class "Default")
      (node (ref "LED48") (pin "4") (pinfunction "DO_4") (pintype "output"))
      (node (ref "LED49") (pin "1") (pinfunction "DI_1") (pintype "input"))
    )
    (net (code "54") (name "Net-(LED49-DO)") (class "Default")
      (node (ref "LED49") (pin "4") (pinfunction "DO_4") (pintype "output"))
      (node (ref "LED50") (pin "1") (pinfunction "DI_1") (pintype "input"))
    )
    (net (code "55") (name "Net-(LED50-DO)") (class "Default")
      (node (ref "LED50") (pin "4") (pinfunction "DO_4") (pintype "output"))
      (node (ref "LED51") (pin "1") (pinfunction "DI_1") (pintype "input"))
    )
    (net (code "56") (name "Net-(LED51-DO)") (class "Default")
      (node (ref "LED51") (pin "4") (pinfunction "DO_4") (pintype "output"))
      (node (ref "LED52") (pin "1") (pinfunction "DI_1") (pintype "input"))
    )
    (net (code "57") (name "Net-(LED52-DO)") (class "Default")
      (node (ref "LED52") (pin "4") (pinfunction "DO_4") (pintype "output"))
      (node (ref "LED53") (pin "1") (pinfunction "DI_1") (pintype "input"))
    )
    (net (code "58") (name "Net-(LED53-DO)") (class "Default")
      (node (ref "LED53") (pin "4") (pinfunction "DO_4") (pintype "output"))
      (node (ref "LED54") (pin "1") (pinfunction "DI_1") (pintype "input"))
    )
    (net (code "59") (name "Net-(LED54-DO)") (class "Default")
      (node (ref "LED54") (pin "4") (pinfunction "DO_4") (pintype "output"))
      (node (ref "LED55") (pin "1") (pinfunction "DI_1") (pintype "input"))
    )
    (net (code "60") (name "Net-(LED55-DO)") (class "Default")
      (node (ref "LED55") (pin "4") (pinfunction "DO_4") (pintype "output"))
      (node (ref "LED56") (pin "1") (pinfunction "DI_1") (pintype "input"))
    )
    (net (code "61") (name "Net-(LED56-DO)") (class "Default")
      (node (ref "LED56") (pin "4") (pinfunction "DO_4") (pintype "output"))
      (node (ref "LED57") (pin "1") (pinfunction "DI_1") (pintype "input"))
    )
    (net (code "62") (name "Net-(LED57-DO)") (class "Default")
      (node (ref "LED57") (pin "4") (pinfunction "DO_4") (pintype "output"))
      (node (ref "LED58") (pin "1") (pinfunction "DI_1") (pintype "input"))
    )
    (net (code "63") (name "Net-(LED58-DO)") (class "Default")
      (node (ref "LED58") (pin "4") (pinfunction "DO_4") (pintype "output"))
      (node (ref "LED59") (pin "1") (pinfunction "DI_1") (pintype "input"))
    )
    (net (code "64") (name "Net-(LED59-DO)") (class "Default")
      (node (ref "LED59") (pin "4") (pinfunction "DO_4") (pintype "output"))
      (node (ref "LED60") (pin "1") (pinfunction "DI_1") (pintype "input"))
    )
    (net (code "65") (name "Net-(LED60-DO)") (class "Default")
      (node (ref "LED60") (pin "4") (pinfunction "DO_4") (pintype "output"))
      (node (ref "LED61") (pin "1") (pinfunction "DI_1") (pintype "input"))
    )
    (net (code "66") (name "Net-(LED61-DO)") (class "Default")
      (node (ref "LED61") (pin "4") (pinfunction "DO_4") (pintype "output"))
      (node (ref "LED62") (pin "1") (pinfunction "DI_1") (pintype "input"))
    )
    (net (code "67") (name "Net-(LED62-DO)") (class "Default")
      (node (ref "LED62") (pin "4") (pinfunction "DO_4") (pintype "output"))
      (node (ref "LED63") (pin "1") (pinfunction "DI_1") (pintype "input"))
    )
    (net (code "68") (name "Net-(LED63-DO)") (class "Default")
      (node (ref "LED63") (pin "4") (pinfunction "DO_4") (pintype "output"))
      (node (ref "LED64") (pin "1") (pinfunction "DI_1") (pintype "input"))
    )
    (net (code "69") (name "Net-(LED64-DO)") (class "Default")
      (node (ref "LED64") (pin "4") (pinfunction "DO_4") (pintype "output"))
      (node (ref "LED65") (pin "1") (pinfunction "DI_1") (pintype "input"))
    )
    (net (code "70") (name "Net-(LED65-DO)") (class "Default")
      (node (ref "LED65") (pin "4") (pinfunction "DO_4") (pintype "output"))
      (node (ref "LED66") (pin "1") (pinfunction "DI_1") (pintype "input"))
    )
    (net (code "71") (name "Net-(LED66-DO)") (class "Default")
      (node (ref "LED66") (pin "4") (pinfunction "DO_4") (pintype "output"))
      (node (ref "LED67") (pin "1") (pinfunction "DI_1") (pintype "input"))
    )
    (net (code "72") (name "Net-(LED67-DO)") (class "Default")
      (node (ref "LED67") (pin "4") (pinfunction "DO_4") (pintype "output"))
      (node (ref "LED68") (pin "1") (pinfunction "DI_1") (pintype "input"))
    )
    (net (code "73") (name "Net-(LED68-DO)") (class "Default")
      (node (ref "LED68") (pin "4") (pinfunction "DO_4") (pintype "output"))
      (node (ref "LED69") (pin "1") (pinfunction "DI_1") (pintype "input"))
    )
    (net (code "74") (name "Net-(LED69-DO)") (class "Default")
      (node (ref "LED69") (pin "4") (pinfunction "DO_4") (pintype "output"))
      (node (ref "LED70") (pin "1") (pinfunction "DI_1") (pintype "input"))
    )
    (net (code "75") (name "VCC") (class "Default")
      (node (ref "JP1") (pin "1") (pinfunction "1_1") (pintype "passive"))
      (node (ref "LED1") (pin "2") (pinfunction "VDD_2") (pintype "power_in"))
      (node (ref "LED10") (pin "2") (pinfunction "VDD_2") (pintype "power_in"))
      (node (ref "LED11") (pin "2") (pinfunction "VDD_2") (pintype "power_in"))
      (node (ref "LED12") (pin "2") (pinfunction "VDD_2") (pintype "power_in"))
      (node (ref "LED13") (pin "2") (pinfunction "VDD_2") (pintype "power_in"))
      (node (ref "LED14") (pin "2") (pinfunction "VDD_2") (pintype "power_in"))
      (node (ref "LED15") (pin "2") (pinfunction "VDD_2") (pintype "power_in"))
      (node (ref "LED16") (pin "2") (pinfunction "VDD_2") (pintype "power_in"))
      (node (ref "LED17") (pin "2") (pinfunction "VDD_2") (pintype "power_in"))
      (node (ref "LED18") (pin "2") (pinfunction "VDD_2") (pintype "power_in"))
      (node (ref "LED19") (pin "2") (pinfunction "VDD_2") (pintype "power_in"))
      (node (ref "LED2") (pin "2") (pinfunction "VDD_2") (pintype "power_in"))
      (node (ref "LED20") (pin "2") (pinfunction "VDD_2") (pintype "power_in"))
      (node (ref "LED21") (pin "2") (pinfunction "VDD_2") (pintype "power_in"))
      (node (ref "LED22") (pin "2") (pinfunction "VDD_2") (pintype "power_in"))
      (node (ref "LED23") (pin "2") (pinfunction "VDD_2") (pintype "power_in"))
      (node (ref "LED24") (pin "2") (pinfunction "VDD_2") (pintype "power_in"))
      (node (ref "LED25") (pin "2") (pinfunction "VDD_2") (pintype "power_in"))
      (node (ref "LED26") (pin "2") (pinfunction "VDD_2") (pintype "power_in"))
      (node (ref "LED27") (pin "2") (pinfunction "VDD_2") (pintype "power_in"))
      (node (ref "LED28") (pin "2") (pinfunction "VDD_2") (pintype "power_in"))
      (node (ref "LED29") (pin "2") (pinfunction "VDD_2") (pintype "power_in"))
      (node (ref "LED3") (pin "2") (pinfunction "VDD_2") (pintype "power_in"))
      (node (ref "LED30") (pin "2") (pinfunction "VDD_2") (pintype "power_in"))
      (node (ref "LED31") (pin "2") (pinfunction "VDD_2") (pintype "power_in"))
      (node (ref "LED32") (pin "2") (pinfunction "VDD_2") (pintype "power_in"))
      (node (ref "LED33") (pin "2") (pinfunction "VDD_2") (pintype "power_in"))
      (node (ref "LED34") (pin "2") (pinfunction "VDD_2") (pintype "power_in"))
      (node (ref "LED35") (pin "2") (pinfunction "VDD_2") (pintype "power_in"))
      (node (ref "LED36") (pin "2") (pinfunction "VDD_2") (pintype "power_in"))
      (node (ref "LED37") (pin "2") (pinfunction "VDD_2") (pintype "power_in"))
      (node (ref "LED38") (pin "2") (pinfunction "VDD_2") (pintype "power_in"))
      (node (ref "LED39") (pin "2") (pinfunction "VDD_2") (pintype "power_in"))
      (node (ref "LED4") (pin "2") (pinfunction "VDD_2") (pintype "power_in"))
      (node (ref "LED40") (pin "2") (pinfunction "VDD_2") (pintype "power_in"))
      (node (ref "LED41") (pin "2") (pinfunction "VDD_2") (pintype "power_in"))
      (node (ref "LED42") (pin "2") (pinfunction "VDD_2") (pintype "power_in"))
      (node (ref "LED43") (pin "2") (pinfunction "VDD_2") (pintype "power_in"))
      (node (ref "LED44") (pin "2") (pinfunction "VDD_2") (pintype "power_in"))
      (node (ref "LED45") (pin "2") (pinfunction "VDD_2") (pintype "power_in"))
      (node (ref "LED46") (pin "2") (pinfunction "VDD_2") (pintype "power_in"))
      (node (ref "LED47") (pin "2") (pinfunction "VDD_2") (pintype "power_in"))
      (node (ref "LED48") (pin "2") (pinfunction "VDD_2") (pintype "power_in"))
      (node (ref "LED49") (pin "2") (pinfunction "VDD_2") (pintype "power_in"))
      (node (ref "LED5") (pin "2") (pinfunction "VDD_2") (pintype "power_in"))
      (node (ref "LED50") (pin "2") (pinfunction "VDD_2") (pintype "power_in"))
      (node (ref "LED51") (pin "2") (pinfunction "VDD_2") (pintype "power_in"))
      (node (ref "LED52") (pin "2") (pinfunction "VDD_2") (pintype "power_in"))
      (node (ref "LED53") (pin "2") (pinfunction "VDD_2") (pintype "power_in"))
      (node (ref "LED54") (pin "2") (pinfunction "VDD_2") (pintype "power_in"))
      (node (ref "LED55") (pin "2") (pinfunction "VDD_2") (pintype "power_in"))
      (node (ref "LED56") (pin "2") (pinfunction "VDD_2") (pintype "power_in"))
      (node (ref "LED57") (pin "2") (pinfunction "VDD_2") (pintype "power_in"))
      (node (ref "LED58") (pin "2") (pinfunction "VDD_2") (pintype "power_in"))
      (node (ref "LED59") (pin "2") (pinfunction "VDD_2") (pintype "power_in"))
      (node (ref "LED6") (pin "2") (pinfunction "VDD_2") (pintype "power_in"))
      (node (ref "LED60") (pin "2") (pinfunction "VDD_2") (pintype "power_in"))
      (node (ref "LED61") (pin "2") (pinfunction "VDD_2") (pintype "power_in"))
      (node (ref "LED62") (pin "2") (pinfunction "VDD_2") (pintype "power_in"))
      (node (ref "LED63") (pin "2") (pinfunction "VDD_2") (pintype "power_in"))
      (node (ref "LED64") (pin "2") (pinfunction "VDD_2") (pintype "power_in"))
      (node (ref "LED65") (pin "2") (pinfunction "VDD_2") (pintype "power_in"))
      (node (ref "LED66") (pin "2") (pinfunction "VDD_2") (pintype "power_in"))
      (node (ref "LED67") (pin "2") (pinfunction "VDD_2") (pintype "power_in"))
      (node (ref "LED68") (pin "2") (pinfunction "VDD_2") (pintype "power_in"))
      (node (ref "LED69") (pin "2") (pinfunction "VDD_2") (pintype "power_in"))
      (node (ref "LED7") (pin "2") (pinfunction "VDD_2") (pintype "power_in"))
      (node (ref "LED70") (pin "2") (pinfunction "VDD_2") (pintype "power_in"))
      (node (ref "LED8") (pin "2") (pinfunction "VDD_2") (pintype "power_in"))
      (node (ref "LED9") (pin "2") (pinfunction "VDD_2") (pintype "power_in"))
      (node (ref "SJ1") (pin "2") (pinfunction "2_2") (pintype "passive"))
    )
    (net (code "76") (name "unconnected-(J1-*D3-PadD3)") (class "Default")
      (node (ref "J1") (pin "D3") (pinfunction "*D3_D3") (pintype "bidirectional"))
    )
    (net (code "77") (name "unconnected-(J1-*D5-PadD5)") (class "Default")
      (node (ref "J1") (pin "D5") (pinfunction "*D5_D5") (pintype "bidirectional"))
    )
    (net (code "78") (name "unconnected-(J1-*D9-PadD9)") (class "Default")
      (node (ref "J1") (pin "D9") (pinfunction "*D9_D9") (pintype "bidirectional"))
    )
    (net (code "79") (name "unconnected-(J1-*D10-PadD10)") (class "Default")
      (node (ref "J1") (pin "D10") (pinfunction "*D10_D10") (pintype "bidirectional"))
    )
    (net (code "80") (name "unconnected-(J1-*D11-PadD11)") (class "Default")
      (node (ref "J1") (pin "D11") (pinfunction "*D11_D11") (pintype "bidirectional"))
    )
    (net (code "81") (name "unconnected-(J1-Pad3.3V)") (class "Default")
      (node (ref "J1") (pin "3.3V") (pinfunction "3.3V_3.3V") (pintype "bidirectional"))
    )
    (net (code "82") (name "unconnected-(J1-PadA0)") (class "Default")
      (node (ref "J1") (pin "A0") (pinfunction "A0_A0") (pintype "bidirectional"))
    )
    (net (code "83") (name "unconnected-(J1-PadA1)") (class "Default")
      (node (ref "J1") (pin "A1") (pinfunction "A1_A1") (pintype "bidirectional"))
    )
    (net (code "84") (name "unconnected-(J1-PadA2)") (class "Default")
      (node (ref "J1") (pin "A2") (pinfunction "A2_A2") (pintype "bidirectional"))
    )
    (net (code "85") (name "unconnected-(J1-PadA3)") (class "Default")
      (node (ref "J1") (pin "A3") (pinfunction "A3_A3") (pintype "bidirectional"))
    )
    (net (code "86") (name "unconnected-(J1-PadA4)") (class "Default")
      (node (ref "J1") (pin "A4") (pinfunction "A4_A4") (pintype "bidirectional"))
    )
    (net (code "87") (name "unconnected-(J1-PadA5)") (class "Default")
      (node (ref "J1") (pin "A5") (pinfunction "A5_A5") (pintype "bidirectional"))
    )
    (net (code "88") (name "unconnected-(J1-PadAREF)") (class "Default")
      (node (ref "J1") (pin "AREF") (pinfunction "AREF_AREF") (pintype "bidirectional"))
    )
    (net (code "89") (name "unconnected-(J1-PadD2)") (class "Default")
      (node (ref "J1") (pin "D2") (pinfunction "D2_D2") (pintype "bidirectional"))
    )
    (net (code "90") (name "unconnected-(J1-PadD4)") (class "Default")
      (node (ref "J1") (pin "D4") (pinfunction "D4_D4") (pintype "bidirectional"))
    )
    (net (code "91") (name "unconnected-(J1-PadD7)") (class "Default")
      (node (ref "J1") (pin "D7") (pinfunction "D7_D7") (pintype "bidirectional"))
    )
    (net (code "92") (name "unconnected-(J1-PadD8)") (class "Default")
      (node (ref "J1") (pin "D8") (pinfunction "D8_D8") (pintype "bidirectional"))
    )
    (net (code "93") (name "unconnected-(J1-PadD12)") (class "Default")
      (node (ref "J1") (pin "D12") (pinfunction "D12_D12") (pintype "bidirectional"))
    )
    (net (code "94") (name "unconnected-(J1-PadD13)") (class "Default")
      (node (ref "J1") (pin "D13") (pinfunction "D13_D13") (pintype "bidirectional"))
    )
    (net (code "95") (name "unconnected-(J1-PadIOREF)") (class "Default")
      (node (ref "J1") (pin "IOREF") (pinfunction "IOREF_IOREF") (pintype "bidirectional"))
    )
    (net (code "96") (name "unconnected-(J1-PadRES)") (class "Default")
      (node (ref "J1") (pin "RES") (pinfunction "RES_RES") (pintype "bidirectional"))
    )
    (net (code "97") (name "unconnected-(J1-PadRX)") (class "Default")
      (node (ref "J1") (pin "RX") (pinfunction "RX_RX") (pintype "bidirectional"))
    )
    (net (code "98") (name "unconnected-(J1-PadSCL)") (class "Default")
      (node (ref "J1") (pin "SCL") (pinfunction "SCL_SCL") (pintype "bidirectional"))
    )
    (net (code "99") (name "unconnected-(J1-PadSDA)") (class "Default")
      (node (ref "J1") (pin "SDA") (pinfunction "SDA_SDA") (pintype "bidirectional"))
    )
    (net (code "100") (name "unconnected-(J1-PadTX)") (class "Default")
      (node (ref "J1") (pin "TX") (pinfunction "TX_TX") (pintype "bidirectional"))
    )
    (net (code "101") (name "unconnected-(J1-PadVIN)") (class "Default")
      (node (ref "J1") (pin "VIN") (pinfunction "VIN_VIN") (pintype "bidirectional"))
    )
  )
)
